# ISP_Pogo_Board.net
KiCad netlist of a schematic drawn in EAGLE
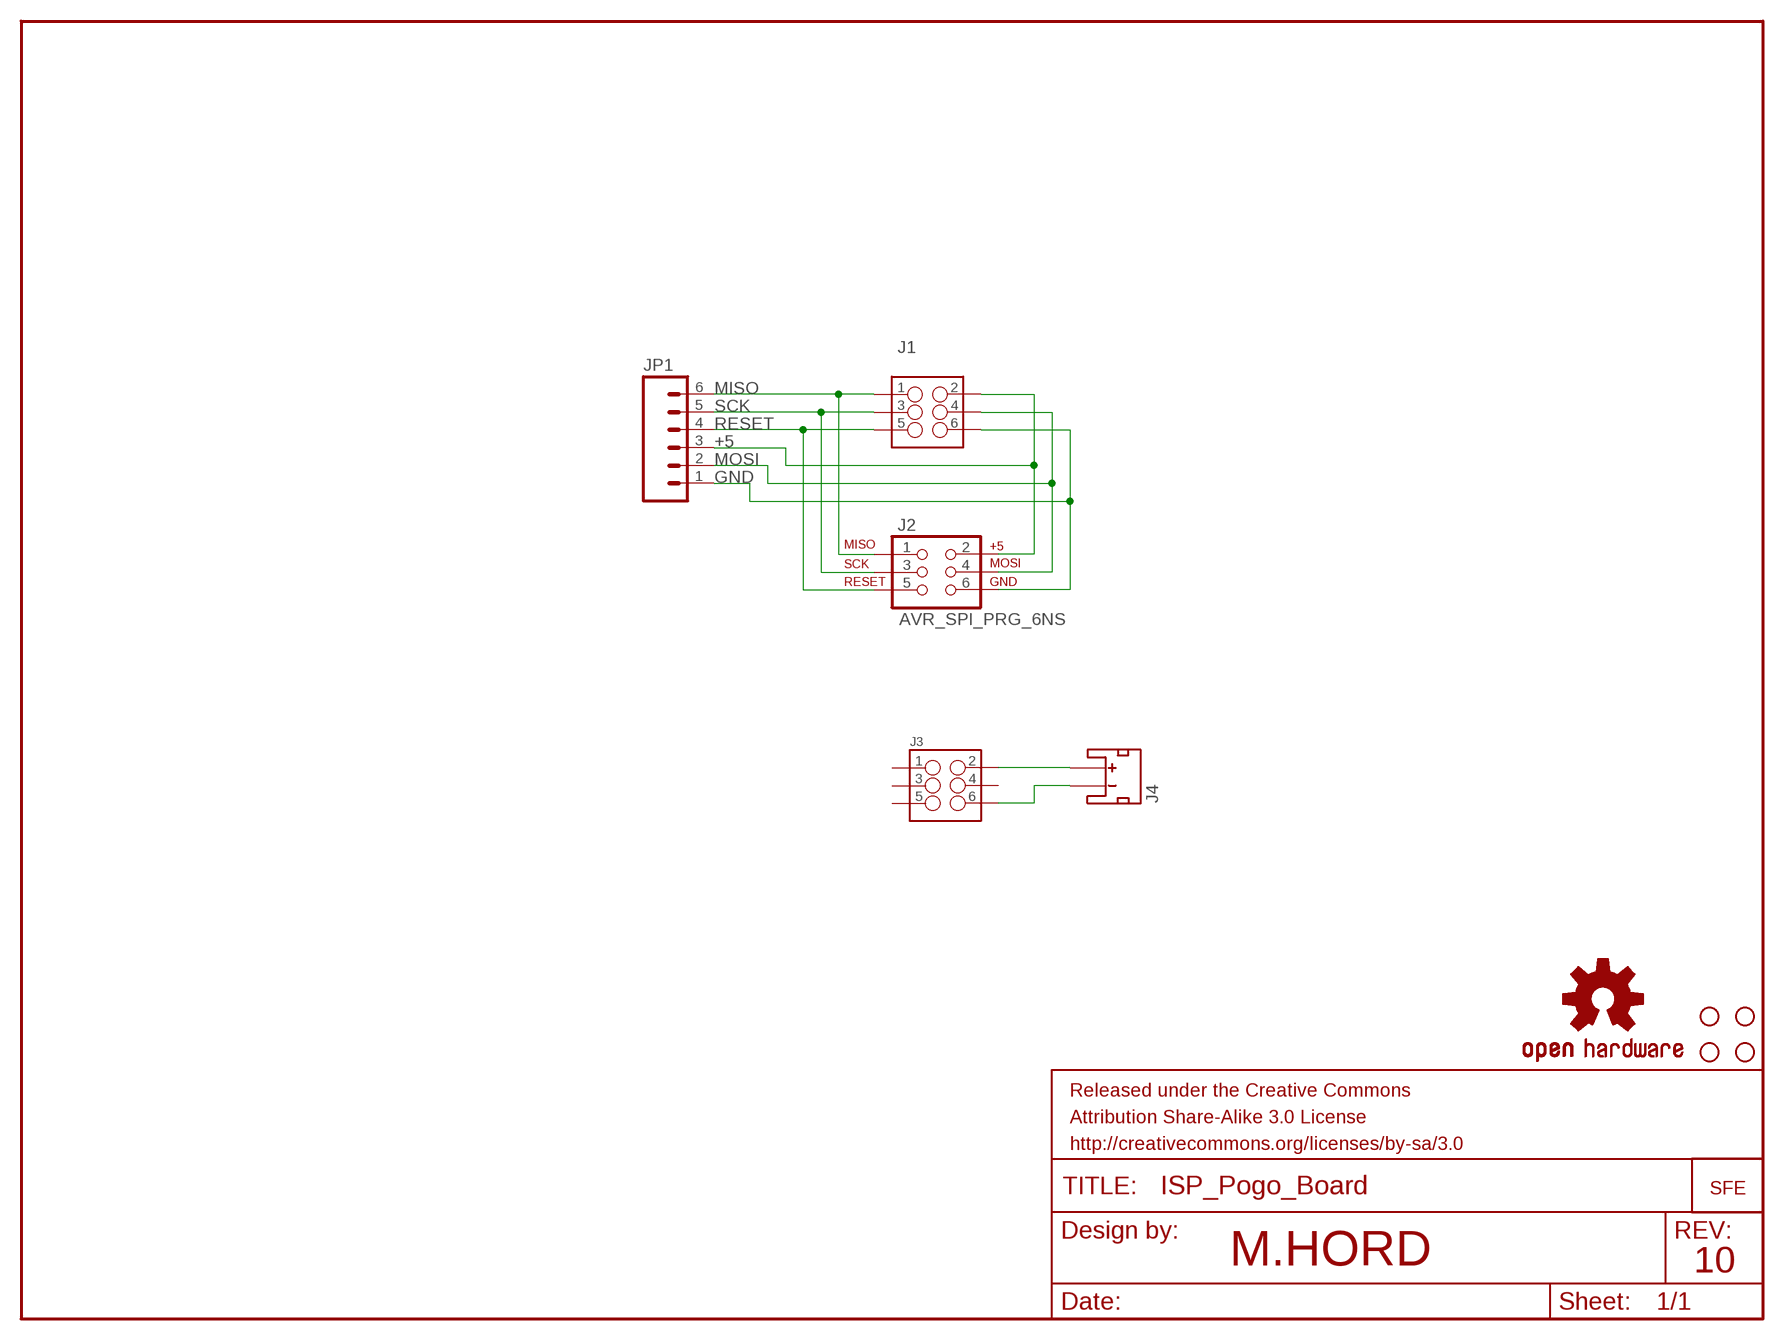
[diagram p0: schematic, sheet 1]

(export (version "E")
  (design (tool "Eeschema 10.0.6"))
  (components
    (comp (ref "FRAME1")
      (value "FRAME-LETTER")
      (footprint "eagle-import:CREATIVE_COMMONS")
      (libsource (lib "eagle-import") (part "FRAME-LETTER"))
    )
    (comp (ref "J1")
      (value "M03X2POGO_PINS")
      (footprint "eagle-import:2X3_POGO")
      (libsource (lib "eagle-import") (part "M03X2POGO_PINS"))
    )
    (comp (ref "J2")
      (value "AVR_SPI_PRG_6NS")
      (footprint "eagle-import:2X3-NS")
      (libsource (lib "eagle-import") (part "AVR_SPI_PRG_6NS"))
    )
    (comp (ref "J3")
      (value "M03X2POGO_PINS")
      (footprint "eagle-import:2X3_POGO")
      (libsource (lib "eagle-import") (part "M03X2POGO_PINS"))
    )
    (comp (ref "J4")
      (value "JST_2MM_MALE")
      (footprint "eagle-import:JST-2-SMD")
      (libsource (lib "eagle-import") (part "JST_2MM_MALE"))
    )
    (comp (ref "JP1")
      (value "M06POLAR")
      (footprint "eagle-import:MOLEX-1X6")
      (libsource (lib "eagle-import") (part "M06POLAR"))
    )
    (comp (ref "JP2")
      (value "STAND-OFF")
      (footprint "eagle-import:STAND-OFF")
      (libsource (lib "eagle-import") (part "STAND-OFF"))
    )
    (comp (ref "JP3")
      (value "STAND-OFF")
      (footprint "eagle-import:STAND-OFF")
      (libsource (lib "eagle-import") (part "STAND-OFF"))
    )
    (comp (ref "JP4")
      (value "STAND-OFF")
      (footprint "eagle-import:STAND-OFF")
      (libsource (lib "eagle-import") (part "STAND-OFF"))
    )
    (comp (ref "JP5")
      (value "STAND-OFF")
      (footprint "eagle-import:STAND-OFF")
      (libsource (lib "eagle-import") (part "STAND-OFF"))
    )
    (comp (ref "JP6")
      (value "LOGO-SFENW2")
      (footprint "eagle-import:SFE-NEW-WEB")
      (libsource (lib "eagle-import") (part "LOGO-SFENW2"))
    )
    (comp (ref "U$1")
      (value "OSHW-LOGOS")
      (footprint "eagle-import:OSHW-LOGO-S")
      (libsource (lib "eagle-import") (part "OSHW-LOGOS"))
    )
  )
  (nets
    (net (code "1") (name "/+5") (class "Default")
      (node (ref "J1") (pin "P$2") (pinfunction "2_P$2") (pintype "bidirectional"))
      (node (ref "J2") (pin "2") (pinfunction "2_2") (pintype "passive"))
      (node (ref "JP1") (pin "3") (pinfunction "3_3") (pintype "passive"))
    )
    (net (code "2") (name "/GND") (class "Default")
      (node (ref "J1") (pin "P$6") (pinfunction "6_P$6") (pintype "bidirectional"))
      (node (ref "J2") (pin "6") (pinfunction "6_6") (pintype "passive"))
      (node (ref "JP1") (pin "1") (pinfunction "1_1") (pintype "passive"))
    )
    (net (code "3") (name "/MISO") (class "Default")
      (node (ref "J1") (pin "P$1") (pinfunction "1_P$1") (pintype "bidirectional"))
      (node (ref "J2") (pin "1") (pinfunction "1_1") (pintype "passive"))
      (node (ref "JP1") (pin "6") (pinfunction "6_6") (pintype "passive"))
    )
    (net (code "4") (name "/MOSI") (class "Default")
      (node (ref "J1") (pin "P$4") (pinfunction "4_P$4") (pintype "bidirectional"))
      (node (ref "J2") (pin "4") (pinfunction "4_4") (pintype "passive"))
      (node (ref "JP1") (pin "2") (pinfunction "2_2") (pintype "passive"))
    )
    (net (code "5") (name "/RESET") (class "Default")
      (node (ref "J1") (pin "P$5") (pinfunction "5_P$5") (pintype "bidirectional"))
      (node (ref "J2") (pin "5") (pinfunction "5_5") (pintype "passive"))
      (node (ref "JP1") (pin "4") (pinfunction "4_4") (pintype "passive"))
    )
    (net (code "6") (name "/SCK") (class "Default")
      (node (ref "J1") (pin "P$3") (pinfunction "3_P$3") (pintype "bidirectional"))
      (node (ref "J2") (pin "3") (pinfunction "3_3") (pintype "passive"))
      (node (ref "JP1") (pin "5") (pinfunction "5_5") (pintype "passive"))
    )
    (net (code "7") (name "Net-(J3-2)") (class "Default")
      (node (ref "J3") (pin "P$2") (pinfunction "2_P$2") (pintype "bidirectional"))
      (node (ref "J4") (pin "2") (pinfunction "+_2") (pintype "bidirectional"))
    )
    (net (code "8") (name "Net-(J3-6)") (class "Default")
      (node (ref "J3") (pin "P$6") (pinfunction "6_P$6") (pintype "bidirectional"))
      (node (ref "J4") (pin "1") (pinfunction "-_1") (pintype "bidirectional"))
    )
    (net (code "9") (name "unconnected-(J3-1-PadP$1)") (class "Default")
      (node (ref "J3") (pin "P$1") (pinfunction "1_P$1") (pintype "bidirectional"))
    )
    (net (code "10") (name "unconnected-(J3-3-PadP$3)") (class "Default")
      (node (ref "J3") (pin "P$3") (pinfunction "3_P$3") (pintype "bidirectional"))
    )
    (net (code "11") (name "unconnected-(J3-4-PadP$4)") (class "Default")
      (node (ref "J3") (pin "P$4") (pinfunction "4_P$4") (pintype "bidirectional"))
    )
    (net (code "12") (name "unconnected-(J3-5-PadP$5)") (class "Default")
      (node (ref "J3") (pin "P$5") (pinfunction "5_P$5") (pintype "bidirectional"))
    )
    (net (code "13") (name "unconnected-(J4-PAD1-PadNC1)") (class "Default")
      (node (ref "J4") (pin "NC1") (pinfunction "PAD1_NC1") (pintype "bidirectional"))
    )
    (net (code "14") (name "unconnected-(J4-PAD2-PadNC2)") (class "Default")
      (node (ref "J4") (pin "NC2") (pinfunction "PAD2_NC2") (pintype "bidirectional"))
    )
  )
)
